# S-Puck-no_mcu.net
KiCad netlist of a schematic drawn in EAGLE
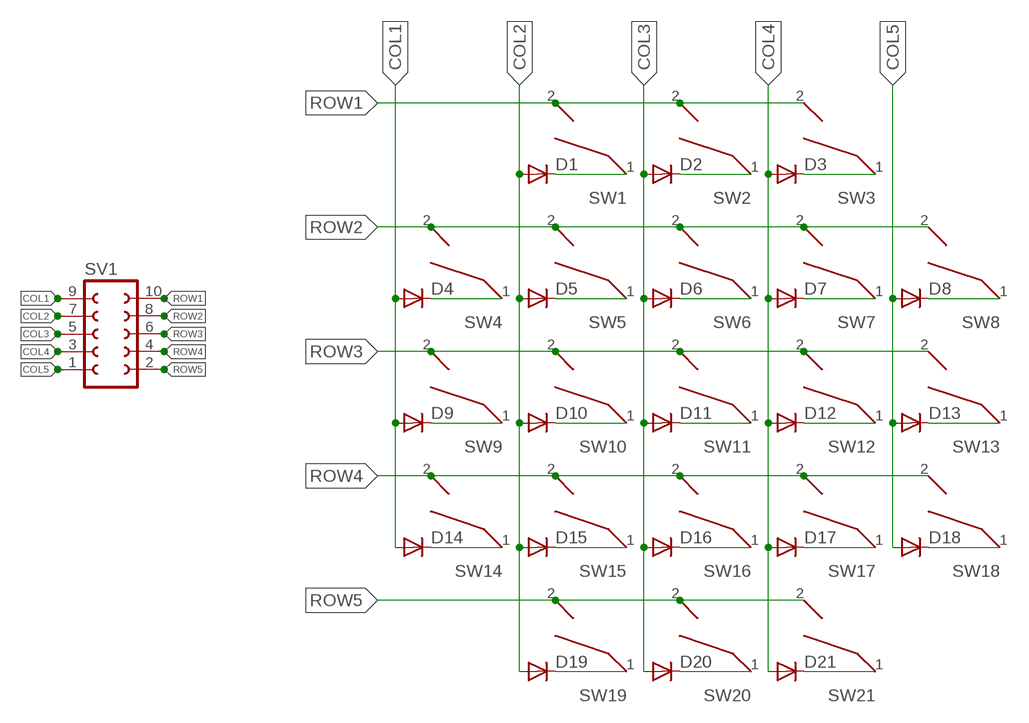
[diagram p0: schematic, sheet 1]

(export (version "E")
  (design (tool "Eeschema 10.0.6"))
  (components
    (comp (ref "D1")
      (value "1N4148DO35-10")
      (footprint "eagle-import:DO35-10")
      (libsource (lib "eagle-import") (part "1N4148DO35-10"))
    )
    (comp (ref "D2")
      (value "1N4148DO35-10")
      (footprint "eagle-import:DO35-10")
      (libsource (lib "eagle-import") (part "1N4148DO35-10"))
    )
    (comp (ref "D3")
      (value "1N4148DO35-10")
      (footprint "eagle-import:DO35-10")
      (libsource (lib "eagle-import") (part "1N4148DO35-10"))
    )
    (comp (ref "D4")
      (value "1N4148DO35-10")
      (footprint "eagle-import:DO35-10")
      (libsource (lib "eagle-import") (part "1N4148DO35-10"))
    )
    (comp (ref "D5")
      (value "1N4148DO35-10")
      (footprint "eagle-import:DO35-10")
      (libsource (lib "eagle-import") (part "1N4148DO35-10"))
    )
    (comp (ref "D6")
      (value "1N4148DO35-10")
      (footprint "eagle-import:DO35-10")
      (libsource (lib "eagle-import") (part "1N4148DO35-10"))
    )
    (comp (ref "D7")
      (value "1N4148DO35-10")
      (footprint "eagle-import:DO35-10")
      (libsource (lib "eagle-import") (part "1N4148DO35-10"))
    )
    (comp (ref "D8")
      (value "1N4148DO35-10")
      (footprint "eagle-import:DO35-10")
      (libsource (lib "eagle-import") (part "1N4148DO35-10"))
    )
    (comp (ref "D9")
      (value "1N4148DO35-10")
      (footprint "eagle-import:DO35-10")
      (libsource (lib "eagle-import") (part "1N4148DO35-10"))
    )
    (comp (ref "D10")
      (value "1N4148DO35-10")
      (footprint "eagle-import:DO35-10")
      (libsource (lib "eagle-import") (part "1N4148DO35-10"))
    )
    (comp (ref "D11")
      (value "1N4148DO35-10")
      (footprint "eagle-import:DO35-10")
      (libsource (lib "eagle-import") (part "1N4148DO35-10"))
    )
    (comp (ref "D12")
      (value "1N4148DO35-10")
      (footprint "eagle-import:DO35-10")
      (libsource (lib "eagle-import") (part "1N4148DO35-10"))
    )
    (comp (ref "D13")
      (value "1N4148DO35-10")
      (footprint "eagle-import:DO35-10")
      (libsource (lib "eagle-import") (part "1N4148DO35-10"))
    )
    (comp (ref "D14")
      (value "1N4148DO35-10")
      (footprint "eagle-import:DO35-10")
      (libsource (lib "eagle-import") (part "1N4148DO35-10"))
    )
    (comp (ref "D15")
      (value "1N4148DO35-10")
      (footprint "eagle-import:DO35-10")
      (libsource (lib "eagle-import") (part "1N4148DO35-10"))
    )
    (comp (ref "D16")
      (value "1N4148DO35-10")
      (footprint "eagle-import:DO35-10")
      (libsource (lib "eagle-import") (part "1N4148DO35-10"))
    )
    (comp (ref "D17")
      (value "1N4148DO35-10")
      (footprint "eagle-import:DO35-10")
      (libsource (lib "eagle-import") (part "1N4148DO35-10"))
    )
    (comp (ref "D18")
      (value "1N4148DO35-10")
      (footprint "eagle-import:DO35-10")
      (libsource (lib "eagle-import") (part "1N4148DO35-10"))
    )
    (comp (ref "D19")
      (value "1N4148DO35-10")
      (footprint "eagle-import:DO35-10")
      (libsource (lib "eagle-import") (part "1N4148DO35-10"))
    )
    (comp (ref "D20")
      (value "1N4148DO35-10")
      (footprint "eagle-import:DO35-10")
      (libsource (lib "eagle-import") (part "1N4148DO35-10"))
    )
    (comp (ref "D21")
      (value "1N4148DO35-10")
      (footprint "eagle-import:DO35-10")
      (libsource (lib "eagle-import") (part "1N4148DO35-10"))
    )
    (comp (ref "SV1")
      (value "FE05-2")
      (footprint "eagle-import:FE05-2")
      (libsource (lib "eagle-import") (part "FE05-2"))
    )
    (comp (ref "SW1")
      (value "CHERRY_MX_WITH_FIXING_PINS")
      (footprint "eagle-import:MX1A-XXNW")
      (libsource (lib "eagle-import") (part "CHERRY_MX_WITH_FIXING_PINS"))
    )
    (comp (ref "SW2")
      (value "CHERRY_MX_WITH_FIXING_PINS")
      (footprint "eagle-import:MX1A-XXNW")
      (libsource (lib "eagle-import") (part "CHERRY_MX_WITH_FIXING_PINS"))
    )
    (comp (ref "SW3")
      (value "CHERRY_MX_WITH_FIXING_PINS")
      (footprint "eagle-import:MX1A-XXNW")
      (libsource (lib "eagle-import") (part "CHERRY_MX_WITH_FIXING_PINS"))
    )
    (comp (ref "SW4")
      (value "CHERRY_MX_WITH_FIXING_PINS")
      (footprint "eagle-import:MX1A-XXNW")
      (libsource (lib "eagle-import") (part "CHERRY_MX_WITH_FIXING_PINS"))
    )
    (comp (ref "SW5")
      (value "CHERRY_MX_WITH_FIXING_PINS")
      (footprint "eagle-import:MX1A-XXNW")
      (libsource (lib "eagle-import") (part "CHERRY_MX_WITH_FIXING_PINS"))
    )
    (comp (ref "SW6")
      (value "CHERRY_MX_WITH_FIXING_PINS")
      (footprint "eagle-import:MX1A-XXNW")
      (libsource (lib "eagle-import") (part "CHERRY_MX_WITH_FIXING_PINS"))
    )
    (comp (ref "SW7")
      (value "CHERRY_MX_WITH_FIXING_PINS")
      (footprint "eagle-import:MX1A-XXNW")
      (libsource (lib "eagle-import") (part "CHERRY_MX_WITH_FIXING_PINS"))
    )
    (comp (ref "SW8")
      (value "CHERRY_MX_WITH_FIXING_PINS")
      (footprint "eagle-import:MX1A-XXNW")
      (libsource (lib "eagle-import") (part "CHERRY_MX_WITH_FIXING_PINS"))
    )
    (comp (ref "SW9")
      (value "CHERRY_MX_WITH_FIXING_PINS")
      (footprint "eagle-import:MX1A-XXNW")
      (libsource (lib "eagle-import") (part "CHERRY_MX_WITH_FIXING_PINS"))
    )
    (comp (ref "SW10")
      (value "CHERRY_MX_WITH_FIXING_PINS")
      (footprint "eagle-import:MX1A-XXNW")
      (libsource (lib "eagle-import") (part "CHERRY_MX_WITH_FIXING_PINS"))
    )
    (comp (ref "SW11")
      (value "CHERRY_MX_WITH_FIXING_PINS")
      (footprint "eagle-import:MX1A-XXNW")
      (libsource (lib "eagle-import") (part "CHERRY_MX_WITH_FIXING_PINS"))
    )
    (comp (ref "SW12")
      (value "CHERRY_MX_WITH_FIXING_PINS")
      (footprint "eagle-import:MX1A-XXNW")
      (libsource (lib "eagle-import") (part "CHERRY_MX_WITH_FIXING_PINS"))
    )
    (comp (ref "SW13")
      (value "CHERRY_MX_WITH_FIXING_PINS")
      (footprint "eagle-import:MX1A-XXNW")
      (libsource (lib "eagle-import") (part "CHERRY_MX_WITH_FIXING_PINS"))
    )
    (comp (ref "SW14")
      (value "CHERRY_MX_WITH_FIXING_PINS")
      (footprint "eagle-import:MX1A-XXNW")
      (libsource (lib "eagle-import") (part "CHERRY_MX_WITH_FIXING_PINS"))
    )
    (comp (ref "SW15")
      (value "CHERRY_MX_WITH_FIXING_PINS")
      (footprint "eagle-import:MX1A-XXNW")
      (libsource (lib "eagle-import") (part "CHERRY_MX_WITH_FIXING_PINS"))
    )
    (comp (ref "SW16")
      (value "CHERRY_MX_WITH_FIXING_PINS")
      (footprint "eagle-import:MX1A-XXNW")
      (libsource (lib "eagle-import") (part "CHERRY_MX_WITH_FIXING_PINS"))
    )
    (comp (ref "SW17")
      (value "CHERRY_MX_WITH_FIXING_PINS")
      (footprint "eagle-import:MX1A-XXNW")
      (libsource (lib "eagle-import") (part "CHERRY_MX_WITH_FIXING_PINS"))
    )
    (comp (ref "SW18")
      (value "CHERRY_MX_WITH_FIXING_PINS")
      (footprint "eagle-import:MX1A-XXNW")
      (libsource (lib "eagle-import") (part "CHERRY_MX_WITH_FIXING_PINS"))
    )
    (comp (ref "SW19")
      (value "CHERRY_MX_WITH_FIXING_PINS")
      (footprint "eagle-import:MX1A-XXNW")
      (libsource (lib "eagle-import") (part "CHERRY_MX_WITH_FIXING_PINS"))
    )
    (comp (ref "SW20")
      (value "CHERRY_MX_WITH_FIXING_PINS")
      (footprint "eagle-import:MX1A-XXNW")
      (libsource (lib "eagle-import") (part "CHERRY_MX_WITH_FIXING_PINS"))
    )
    (comp (ref "SW21")
      (value "CHERRY_MX_WITH_FIXING_PINS")
      (footprint "eagle-import:MX1A-XXNW")
      (libsource (lib "eagle-import") (part "CHERRY_MX_WITH_FIXING_PINS"))
    )
  )
  (nets
    (net (code "1") (name "COL1") (class "Default")
      (node (ref "D14") (pin "A") (pinfunction "A_A") (pintype "passive"))
      (node (ref "D4") (pin "A") (pinfunction "A_A") (pintype "passive"))
      (node (ref "D9") (pin "A") (pinfunction "A_A") (pintype "passive"))
      (node (ref "SV1") (pin "9") (pinfunction "9_9") (pintype "passive"))
    )
    (net (code "2") (name "COL2") (class "Default")
      (node (ref "D1") (pin "A") (pinfunction "A_A") (pintype "passive"))
      (node (ref "D10") (pin "A") (pinfunction "A_A") (pintype "passive"))
      (node (ref "D15") (pin "A") (pinfunction "A_A") (pintype "passive"))
      (node (ref "D19") (pin "A") (pinfunction "A_A") (pintype "passive"))
      (node (ref "D5") (pin "A") (pinfunction "A_A") (pintype "passive"))
      (node (ref "SV1") (pin "7") (pinfunction "7_7") (pintype "passive"))
    )
    (net (code "3") (name "COL3") (class "Default")
      (node (ref "D11") (pin "A") (pinfunction "A_A") (pintype "passive"))
      (node (ref "D16") (pin "A") (pinfunction "A_A") (pintype "passive"))
      (node (ref "D2") (pin "A") (pinfunction "A_A") (pintype "passive"))
      (node (ref "D20") (pin "A") (pinfunction "A_A") (pintype "passive"))
      (node (ref "D6") (pin "A") (pinfunction "A_A") (pintype "passive"))
      (node (ref "SV1") (pin "5") (pinfunction "5_5") (pintype "passive"))
    )
    (net (code "4") (name "COL4") (class "Default")
      (node (ref "D12") (pin "A") (pinfunction "A_A") (pintype "passive"))
      (node (ref "D17") (pin "A") (pinfunction "A_A") (pintype "passive"))
      (node (ref "D21") (pin "A") (pinfunction "A_A") (pintype "passive"))
      (node (ref "D3") (pin "A") (pinfunction "A_A") (pintype "passive"))
      (node (ref "D7") (pin "A") (pinfunction "A_A") (pintype "passive"))
      (node (ref "SV1") (pin "3") (pinfunction "3_3") (pintype "passive"))
    )
    (net (code "5") (name "COL5") (class "Default")
      (node (ref "D13") (pin "A") (pinfunction "A_A") (pintype "passive"))
      (node (ref "D18") (pin "A") (pinfunction "A_A") (pintype "passive"))
      (node (ref "D8") (pin "A") (pinfunction "A_A") (pintype "passive"))
      (node (ref "SV1") (pin "1") (pinfunction "1_1") (pintype "passive"))
    )
    (net (code "6") (name "Net-(D1-PadC)") (class "Default")
      (node (ref "D1") (pin "C") (pinfunction "C_C") (pintype "passive"))
      (node (ref "SW1") (pin "1") (pinfunction "1_1") (pintype "passive"))
    )
    (net (code "7") (name "Net-(D2-PadC)") (class "Default")
      (node (ref "D2") (pin "C") (pinfunction "C_C") (pintype "passive"))
      (node (ref "SW2") (pin "1") (pinfunction "1_1") (pintype "passive"))
    )
    (net (code "8") (name "Net-(D3-PadC)") (class "Default")
      (node (ref "D3") (pin "C") (pinfunction "C_C") (pintype "passive"))
      (node (ref "SW3") (pin "1") (pinfunction "1_1") (pintype "passive"))
    )
    (net (code "9") (name "Net-(D4-PadC)") (class "Default")
      (node (ref "D4") (pin "C") (pinfunction "C_C") (pintype "passive"))
      (node (ref "SW4") (pin "1") (pinfunction "1_1") (pintype "passive"))
    )
    (net (code "10") (name "Net-(D5-PadC)") (class "Default")
      (node (ref "D5") (pin "C") (pinfunction "C_C") (pintype "passive"))
      (node (ref "SW5") (pin "1") (pinfunction "1_1") (pintype "passive"))
    )
    (net (code "11") (name "Net-(D6-PadC)") (class "Default")
      (node (ref "D6") (pin "C") (pinfunction "C_C") (pintype "passive"))
      (node (ref "SW6") (pin "1") (pinfunction "1_1") (pintype "passive"))
    )
    (net (code "12") (name "Net-(D7-PadC)") (class "Default")
      (node (ref "D7") (pin "C") (pinfunction "C_C") (pintype "passive"))
      (node (ref "SW7") (pin "1") (pinfunction "1_1") (pintype "passive"))
    )
    (net (code "13") (name "Net-(D8-PadC)") (class "Default")
      (node (ref "D8") (pin "C") (pinfunction "C_C") (pintype "passive"))
      (node (ref "SW8") (pin "1") (pinfunction "1_1") (pintype "passive"))
    )
    (net (code "14") (name "Net-(D9-PadC)") (class "Default")
      (node (ref "D9") (pin "C") (pinfunction "C_C") (pintype "passive"))
      (node (ref "SW9") (pin "1") (pinfunction "1_1") (pintype "passive"))
    )
    (net (code "15") (name "Net-(D10-PadC)") (class "Default")
      (node (ref "D10") (pin "C") (pinfunction "C_C") (pintype "passive"))
      (node (ref "SW10") (pin "1") (pinfunction "1_1") (pintype "passive"))
    )
    (net (code "16") (name "Net-(D11-PadC)") (class "Default")
      (node (ref "D11") (pin "C") (pinfunction "C_C") (pintype "passive"))
      (node (ref "SW11") (pin "1") (pinfunction "1_1") (pintype "passive"))
    )
    (net (code "17") (name "Net-(D12-PadC)") (class "Default")
      (node (ref "D12") (pin "C") (pinfunction "C_C") (pintype "passive"))
      (node (ref "SW12") (pin "1") (pinfunction "1_1") (pintype "passive"))
    )
    (net (code "18") (name "Net-(D13-PadC)") (class "Default")
      (node (ref "D13") (pin "C") (pinfunction "C_C") (pintype "passive"))
      (node (ref "SW13") (pin "1") (pinfunction "1_1") (pintype "passive"))
    )
    (net (code "19") (name "Net-(D14-PadC)") (class "Default")
      (node (ref "D14") (pin "C") (pinfunction "C_C") (pintype "passive"))
      (node (ref "SW14") (pin "1") (pinfunction "1_1") (pintype "passive"))
    )
    (net (code "20") (name "Net-(D15-PadC)") (class "Default")
      (node (ref "D15") (pin "C") (pinfunction "C_C") (pintype "passive"))
      (node (ref "SW15") (pin "1") (pinfunction "1_1") (pintype "passive"))
    )
    (net (code "21") (name "Net-(D16-PadC)") (class "Default")
      (node (ref "D16") (pin "C") (pinfunction "C_C") (pintype "passive"))
      (node (ref "SW16") (pin "1") (pinfunction "1_1") (pintype "passive"))
    )
    (net (code "22") (name "Net-(D17-PadC)") (class "Default")
      (node (ref "D17") (pin "C") (pinfunction "C_C") (pintype "passive"))
      (node (ref "SW17") (pin "1") (pinfunction "1_1") (pintype "passive"))
    )
    (net (code "23") (name "Net-(D18-PadC)") (class "Default")
      (node (ref "D18") (pin "C") (pinfunction "C_C") (pintype "passive"))
      (node (ref "SW18") (pin "1") (pinfunction "1_1") (pintype "passive"))
    )
    (net (code "24") (name "Net-(D19-PadC)") (class "Default")
      (node (ref "D19") (pin "C") (pinfunction "C_C") (pintype "passive"))
      (node (ref "SW19") (pin "1") (pinfunction "1_1") (pintype "passive"))
    )
    (net (code "25") (name "Net-(D20-PadC)") (class "Default")
      (node (ref "D20") (pin "C") (pinfunction "C_C") (pintype "passive"))
      (node (ref "SW20") (pin "1") (pinfunction "1_1") (pintype "passive"))
    )
    (net (code "26") (name "Net-(D21-PadC)") (class "Default")
      (node (ref "D21") (pin "C") (pinfunction "C_C") (pintype "passive"))
      (node (ref "SW21") (pin "1") (pinfunction "1_1") (pintype "passive"))
    )
    (net (code "27") (name "ROW1") (class "Default")
      (node (ref "SV1") (pin "10") (pinfunction "10_10") (pintype "passive"))
      (node (ref "SW1") (pin "2") (pinfunction "2_2") (pintype "passive"))
      (node (ref "SW2") (pin "2") (pinfunction "2_2") (pintype "passive"))
      (node (ref "SW3") (pin "2") (pinfunction "2_2") (pintype "passive"))
    )
    (net (code "28") (name "ROW2") (class "Default")
      (node (ref "SV1") (pin "8") (pinfunction "8_8") (pintype "passive"))
      (node (ref "SW4") (pin "2") (pinfunction "2_2") (pintype "passive"))
      (node (ref "SW5") (pin "2") (pinfunction "2_2") (pintype "passive"))
      (node (ref "SW6") (pin "2") (pinfunction "2_2") (pintype "passive"))
      (node (ref "SW7") (pin "2") (pinfunction "2_2") (pintype "passive"))
      (node (ref "SW8") (pin "2") (pinfunction "2_2") (pintype "passive"))
    )
    (net (code "29") (name "ROW3") (class "Default")
      (node (ref "SV1") (pin "6") (pinfunction "6_6") (pintype "passive"))
      (node (ref "SW10") (pin "2") (pinfunction "2_2") (pintype "passive"))
      (node (ref "SW11") (pin "2") (pinfunction "2_2") (pintype "passive"))
      (node (ref "SW12") (pin "2") (pinfunction "2_2") (pintype "passive"))
      (node (ref "SW13") (pin "2") (pinfunction "2_2") (pintype "passive"))
      (node (ref "SW9") (pin "2") (pinfunction "2_2") (pintype "passive"))
    )
    (net (code "30") (name "ROW4") (class "Default")
      (node (ref "SV1") (pin "4") (pinfunction "4_4") (pintype "passive"))
      (node (ref "SW14") (pin "2") (pinfunction "2_2") (pintype "passive"))
      (node (ref "SW15") (pin "2") (pinfunction "2_2") (pintype "passive"))
      (node (ref "SW16") (pin "2") (pinfunction "2_2") (pintype "passive"))
      (node (ref "SW17") (pin "2") (pinfunction "2_2") (pintype "passive"))
      (node (ref "SW18") (pin "2") (pinfunction "2_2") (pintype "passive"))
    )
    (net (code "31") (name "ROW5") (class "Default")
      (node (ref "SV1") (pin "2") (pinfunction "2_2") (pintype "passive"))
      (node (ref "SW19") (pin "2") (pinfunction "2_2") (pintype "passive"))
      (node (ref "SW20") (pin "2") (pinfunction "2_2") (pintype "passive"))
      (node (ref "SW21") (pin "2") (pinfunction "2_2") (pintype "passive"))
    )
  )
)
